# display.net
KiCad netlist of a schematic drawn in Altium Designer
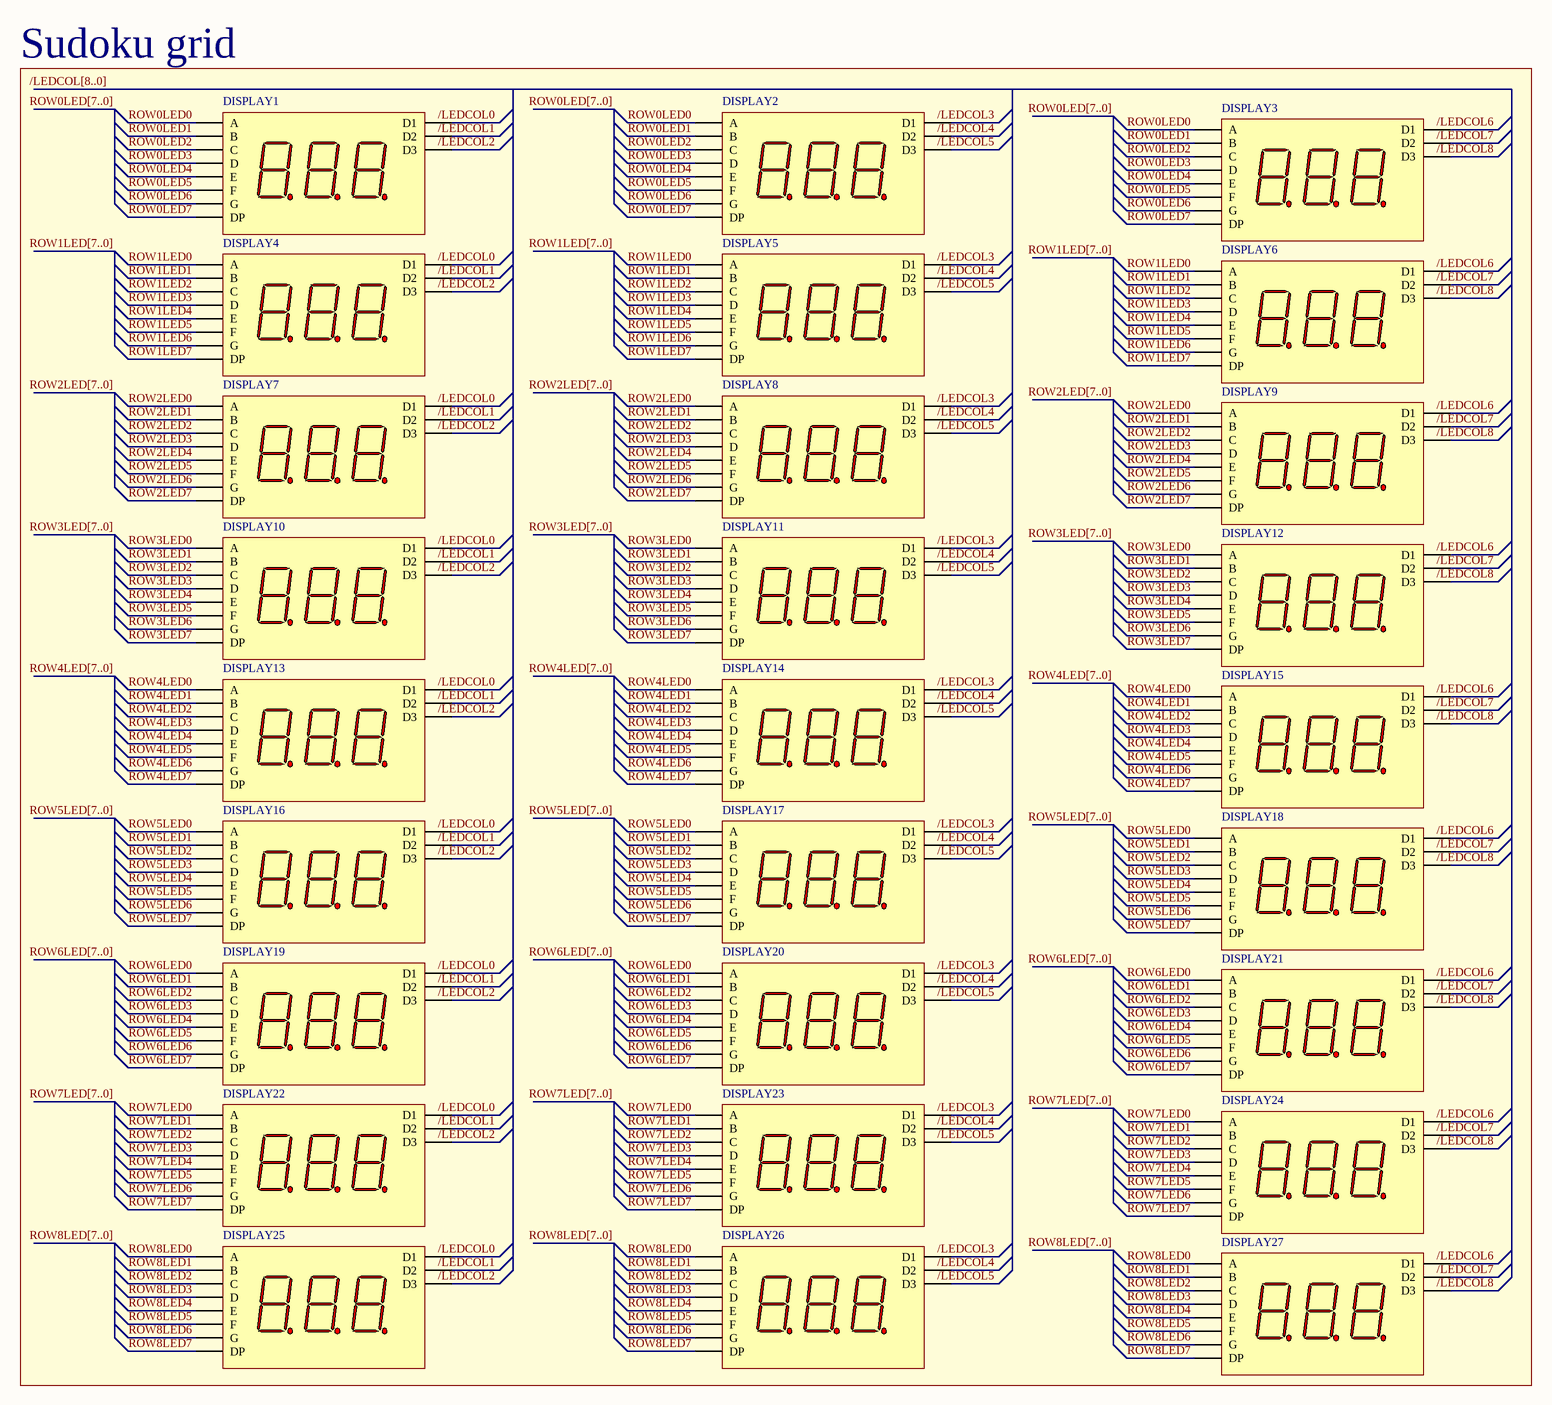
[diagram p0: display.SchDoc]

(export (version "E")
  (design (tool "Eeschema 10.0.6"))
  (components
    (comp (ref "DISPLAY1")
      (value "~")
      (footprint "3DIGITDISPLAY")
      (description "7-Segment Display")
      (fields (field (name "PUBLISHER") "Altium Limited"))
      (libsource (lib "3digit_7seg_display") (part "3DIGITREDCC"))
    )
    (comp (ref "DISPLAY2")
      (value "~")
      (footprint "3DIGITDISPLAY")
      (description "7.62 mm Black Surface HER 7-Segment Display: CC, RH DP")
      (fields (field (name "PUBLISHER") "Altium Limited"))
      (libsource (lib "3digit_7seg_display") (part "3DIGITREDCC"))
    )
    (comp (ref "DISPLAY3")
      (value "~")
      (footprint "3DIGITDISPLAY")
      (description "7.62 mm Black Surface HER 7-Segment Display: CC, RH DP")
      (fields (field (name "PUBLISHER") "Altium Limited"))
      (libsource (lib "3digit_7seg_display") (part "3DIGITREDCC"))
    )
    (comp (ref "DISPLAY4")
      (value "~")
      (footprint "3DIGITDISPLAY")
      (description "7.62 mm Black Surface HER 7-Segment Display: CC, RH DP")
      (fields (field (name "PUBLISHER") "Altium Limited"))
      (libsource (lib "3digit_7seg_display") (part "3DIGITREDCC"))
    )
    (comp (ref "DISPLAY5")
      (value "~")
      (footprint "3DIGITDISPLAY")
      (description "7.62 mm Black Surface HER 7-Segment Display: CC, RH DP")
      (fields (field (name "PUBLISHER") "Altium Limited"))
      (libsource (lib "3digit_7seg_display") (part "3DIGITREDCC"))
    )
    (comp (ref "DISPLAY6")
      (value "~")
      (footprint "3DIGITDISPLAY")
      (description "7.62 mm Black Surface HER 7-Segment Display: CC, RH DP")
      (fields (field (name "PUBLISHER") "Altium Limited"))
      (libsource (lib "3digit_7seg_display") (part "3DIGITREDCC"))
    )
    (comp (ref "DISPLAY7")
      (value "~")
      (footprint "3DIGITDISPLAY")
      (description "7.62 mm Black Surface HER 7-Segment Display: CC, RH DP")
      (fields (field (name "PUBLISHER") "Altium Limited"))
      (libsource (lib "3digit_7seg_display") (part "3DIGITREDCC"))
    )
    (comp (ref "DISPLAY8")
      (value "~")
      (footprint "3DIGITDISPLAY")
      (description "7.62 mm Black Surface HER 7-Segment Display: CC, RH DP")
      (fields (field (name "PUBLISHER") "Altium Limited"))
      (libsource (lib "3digit_7seg_display") (part "3DIGITREDCC"))
    )
    (comp (ref "DISPLAY9")
      (value "~")
      (footprint "3DIGITDISPLAY")
      (description "7.62 mm Black Surface HER 7-Segment Display: CC, RH DP")
      (fields (field (name "PUBLISHER") "Altium Limited"))
      (libsource (lib "3digit_7seg_display") (part "3DIGITREDCC"))
    )
    (comp (ref "DISPLAY10")
      (value "~")
      (footprint "3DIGITDISPLAY")
      (description "7.62 mm Black Surface HER 7-Segment Display: CC, RH DP")
      (fields (field (name "PUBLISHER") "Altium Limited"))
      (libsource (lib "3digit_7seg_display") (part "3DIGITREDCC"))
    )
    (comp (ref "DISPLAY11")
      (value "~")
      (footprint "3DIGITDISPLAY")
      (description "7.62 mm Black Surface HER 7-Segment Display: CC, RH DP")
      (fields (field (name "PUBLISHER") "Altium Limited"))
      (libsource (lib "3digit_7seg_display") (part "3DIGITREDCC"))
    )
    (comp (ref "DISPLAY12")
      (value "~")
      (footprint "3DIGITDISPLAY")
      (description "7.62 mm Black Surface HER 7-Segment Display: CC, RH DP")
      (fields (field (name "PUBLISHER") "Altium Limited"))
      (libsource (lib "3digit_7seg_display") (part "3DIGITREDCC"))
    )
    (comp (ref "DISPLAY13")
      (value "~")
      (footprint "3DIGITDISPLAY")
      (description "7.62 mm Black Surface HER 7-Segment Display: CC, RH DP")
      (fields (field (name "PUBLISHER") "Altium Limited"))
      (libsource (lib "3digit_7seg_display") (part "3DIGITREDCC"))
    )
    (comp (ref "DISPLAY14")
      (value "~")
      (footprint "3DIGITDISPLAY")
      (description "7.62 mm Black Surface HER 7-Segment Display: CC, RH DP")
      (fields (field (name "PUBLISHER") "Altium Limited"))
      (libsource (lib "3digit_7seg_display") (part "3DIGITREDCC"))
    )
    (comp (ref "DISPLAY15")
      (value "~")
      (footprint "3DIGITDISPLAY")
      (description "7.62 mm Black Surface HER 7-Segment Display: CC, RH DP")
      (fields (field (name "PUBLISHER") "Altium Limited"))
      (libsource (lib "3digit_7seg_display") (part "3DIGITREDCC"))
    )
    (comp (ref "DISPLAY16")
      (value "~")
      (footprint "3DIGITDISPLAY")
      (description "7.62 mm Black Surface HER 7-Segment Display: CC, RH DP")
      (fields (field (name "PUBLISHER") "Altium Limited"))
      (libsource (lib "3digit_7seg_display") (part "3DIGITREDCC"))
    )
    (comp (ref "DISPLAY17")
      (value "~")
      (footprint "3DIGITDISPLAY")
      (description "7.62 mm Black Surface HER 7-Segment Display: CC, RH DP")
      (fields (field (name "PUBLISHER") "Altium Limited"))
      (libsource (lib "3digit_7seg_display") (part "3DIGITREDCC"))
    )
    (comp (ref "DISPLAY18")
      (value "~")
      (footprint "3DIGITDISPLAY")
      (description "7.62 mm Black Surface HER 7-Segment Display: CC, RH DP")
      (fields (field (name "PUBLISHER") "Altium Limited"))
      (libsource (lib "3digit_7seg_display") (part "3DIGITREDCC"))
    )
    (comp (ref "DISPLAY19")
      (value "~")
      (footprint "3DIGITDISPLAY")
      (description "7.62 mm Black Surface HER 7-Segment Display: CC, RH DP")
      (fields (field (name "PUBLISHER") "Altium Limited"))
      (libsource (lib "3digit_7seg_display") (part "3DIGITREDCC"))
    )
    (comp (ref "DISPLAY20")
      (value "~")
      (footprint "3DIGITDISPLAY")
      (description "7.62 mm Black Surface HER 7-Segment Display: CC, RH DP")
      (fields (field (name "PUBLISHER") "Altium Limited"))
      (libsource (lib "3digit_7seg_display") (part "3DIGITREDCC"))
    )
    (comp (ref "DISPLAY21")
      (value "~")
      (footprint "3DIGITDISPLAY")
      (description "7.62 mm Black Surface HER 7-Segment Display: CC, RH DP")
      (fields (field (name "PUBLISHER") "Altium Limited"))
      (libsource (lib "3digit_7seg_display") (part "3DIGITREDCC"))
    )
    (comp (ref "DISPLAY22")
      (value "~")
      (footprint "3DIGITDISPLAY")
      (description "7.62 mm Black Surface HER 7-Segment Display: CC, RH DP")
      (fields (field (name "PUBLISHER") "Altium Limited"))
      (libsource (lib "3digit_7seg_display") (part "3DIGITREDCC"))
    )
    (comp (ref "DISPLAY23")
      (value "~")
      (footprint "3DIGITDISPLAY")
      (description "7.62 mm Black Surface HER 7-Segment Display: CC, RH DP")
      (fields (field (name "PUBLISHER") "Altium Limited"))
      (libsource (lib "3digit_7seg_display") (part "3DIGITREDCC"))
    )
    (comp (ref "DISPLAY24")
      (value "~")
      (footprint "3DIGITDISPLAY")
      (description "7.62 mm Black Surface HER 7-Segment Display: CC, RH DP")
      (fields (field (name "PUBLISHER") "Altium Limited"))
      (libsource (lib "3digit_7seg_display") (part "3DIGITREDCC"))
    )
    (comp (ref "DISPLAY25")
      (value "~")
      (footprint "3DIGITDISPLAY")
      (description "7.62 mm Black Surface HER 7-Segment Display: CC, RH DP")
      (fields (field (name "PUBLISHER") "Altium Limited"))
      (libsource (lib "3digit_7seg_display") (part "3DIGITREDCC"))
    )
    (comp (ref "DISPLAY26")
      (value "~")
      (footprint "3DIGITDISPLAY")
      (description "7.62 mm Black Surface HER 7-Segment Display: CC, RH DP")
      (fields (field (name "PUBLISHER") "Altium Limited"))
      (libsource (lib "3digit_7seg_display") (part "3DIGITREDCC"))
    )
    (comp (ref "DISPLAY27")
      (value "~")
      (footprint "3DIGITDISPLAY")
      (description "7.62 mm Black Surface HER 7-Segment Display: CC, RH DP")
      (fields (field (name "PUBLISHER") "Altium Limited"))
      (libsource (lib "3digit_7seg_display") (part "3DIGITREDCC"))
    )
  )
  (nets
    (net (code "10") (name "/ROW0LED0") (class "Default")
      (node (ref "DISPLAY1") (pin "11") (pinfunction "A_11") (pintype "passive"))
      (node (ref "DISPLAY2") (pin "11") (pinfunction "A_11") (pintype "passive"))
      (node (ref "DISPLAY3") (pin "11") (pinfunction "A_11") (pintype "passive"))
    )
    (net (code "11") (name "/ROW0LED1") (class "Default")
      (node (ref "DISPLAY1") (pin "7") (pinfunction "B_7") (pintype "passive"))
      (node (ref "DISPLAY2") (pin "7") (pinfunction "B_7") (pintype "passive"))
      (node (ref "DISPLAY3") (pin "7") (pinfunction "B_7") (pintype "passive"))
    )
    (net (code "12") (name "/ROW0LED2") (class "Default")
      (node (ref "DISPLAY1") (pin "4") (pinfunction "C_4") (pintype "passive"))
      (node (ref "DISPLAY2") (pin "4") (pinfunction "C_4") (pintype "passive"))
      (node (ref "DISPLAY3") (pin "4") (pinfunction "C_4") (pintype "passive"))
    )
    (net (code "13") (name "/ROW0LED3") (class "Default")
      (node (ref "DISPLAY1") (pin "2") (pinfunction "D_2") (pintype "passive"))
      (node (ref "DISPLAY2") (pin "2") (pinfunction "D_2") (pintype "passive"))
      (node (ref "DISPLAY3") (pin "2") (pinfunction "D_2") (pintype "passive"))
    )
    (net (code "14") (name "/ROW0LED4") (class "Default")
      (node (ref "DISPLAY1") (pin "1") (pinfunction "E_1") (pintype "passive"))
      (node (ref "DISPLAY2") (pin "1") (pinfunction "E_1") (pintype "passive"))
      (node (ref "DISPLAY3") (pin "1") (pinfunction "E_1") (pintype "passive"))
    )
    (net (code "15") (name "/ROW0LED5") (class "Default")
      (node (ref "DISPLAY1") (pin "10") (pinfunction "F_10") (pintype "passive"))
      (node (ref "DISPLAY2") (pin "10") (pinfunction "F_10") (pintype "passive"))
      (node (ref "DISPLAY3") (pin "10") (pinfunction "F_10") (pintype "passive"))
    )
    (net (code "16") (name "/ROW0LED6") (class "Default")
      (node (ref "DISPLAY1") (pin "5") (pinfunction "G_5") (pintype "passive"))
      (node (ref "DISPLAY2") (pin "5") (pinfunction "G_5") (pintype "passive"))
      (node (ref "DISPLAY3") (pin "5") (pinfunction "G_5") (pintype "passive"))
    )
    (net (code "17") (name "/ROW0LED7") (class "Default")
      (node (ref "DISPLAY1") (pin "3") (pinfunction "DP_3") (pintype "passive"))
      (node (ref "DISPLAY2") (pin "3") (pinfunction "DP_3") (pintype "passive"))
      (node (ref "DISPLAY3") (pin "3") (pinfunction "DP_3") (pintype "passive"))
    )
    (net (code "19") (name "/ROW1LED0") (class "Default")
      (node (ref "DISPLAY4") (pin "11") (pinfunction "A_11") (pintype "passive"))
      (node (ref "DISPLAY5") (pin "11") (pinfunction "A_11") (pintype "passive"))
      (node (ref "DISPLAY6") (pin "11") (pinfunction "A_11") (pintype "passive"))
    )
    (net (code "20") (name "/ROW1LED1") (class "Default")
      (node (ref "DISPLAY4") (pin "7") (pinfunction "B_7") (pintype "passive"))
      (node (ref "DISPLAY5") (pin "7") (pinfunction "B_7") (pintype "passive"))
      (node (ref "DISPLAY6") (pin "7") (pinfunction "B_7") (pintype "passive"))
    )
    (net (code "21") (name "/ROW1LED2") (class "Default")
      (node (ref "DISPLAY4") (pin "4") (pinfunction "C_4") (pintype "passive"))
      (node (ref "DISPLAY5") (pin "4") (pinfunction "C_4") (pintype "passive"))
      (node (ref "DISPLAY6") (pin "4") (pinfunction "C_4") (pintype "passive"))
    )
    (net (code "22") (name "/ROW1LED3") (class "Default")
      (node (ref "DISPLAY4") (pin "2") (pinfunction "D_2") (pintype "passive"))
      (node (ref "DISPLAY5") (pin "2") (pinfunction "D_2") (pintype "passive"))
      (node (ref "DISPLAY6") (pin "2") (pinfunction "D_2") (pintype "passive"))
    )
    (net (code "23") (name "/ROW1LED4") (class "Default")
      (node (ref "DISPLAY4") (pin "1") (pinfunction "E_1") (pintype "passive"))
      (node (ref "DISPLAY5") (pin "1") (pinfunction "E_1") (pintype "passive"))
      (node (ref "DISPLAY6") (pin "1") (pinfunction "E_1") (pintype "passive"))
    )
    (net (code "24") (name "/ROW1LED5") (class "Default")
      (node (ref "DISPLAY4") (pin "10") (pinfunction "F_10") (pintype "passive"))
      (node (ref "DISPLAY5") (pin "10") (pinfunction "F_10") (pintype "passive"))
      (node (ref "DISPLAY6") (pin "10") (pinfunction "F_10") (pintype "passive"))
    )
    (net (code "25") (name "/ROW1LED6") (class "Default")
      (node (ref "DISPLAY4") (pin "5") (pinfunction "G_5") (pintype "passive"))
      (node (ref "DISPLAY5") (pin "5") (pinfunction "G_5") (pintype "passive"))
      (node (ref "DISPLAY6") (pin "5") (pinfunction "G_5") (pintype "passive"))
    )
    (net (code "26") (name "/ROW1LED7") (class "Default")
      (node (ref "DISPLAY4") (pin "3") (pinfunction "DP_3") (pintype "passive"))
      (node (ref "DISPLAY5") (pin "3") (pinfunction "DP_3") (pintype "passive"))
      (node (ref "DISPLAY6") (pin "3") (pinfunction "DP_3") (pintype "passive"))
    )
    (net (code "28") (name "/ROW2LED0") (class "Default")
      (node (ref "DISPLAY7") (pin "11") (pinfunction "A_11") (pintype "passive"))
      (node (ref "DISPLAY8") (pin "11") (pinfunction "A_11") (pintype "passive"))
      (node (ref "DISPLAY9") (pin "11") (pinfunction "A_11") (pintype "passive"))
    )
    (net (code "29") (name "/ROW2LED1") (class "Default")
      (node (ref "DISPLAY7") (pin "7") (pinfunction "B_7") (pintype "passive"))
      (node (ref "DISPLAY8") (pin "7") (pinfunction "B_7") (pintype "passive"))
      (node (ref "DISPLAY9") (pin "7") (pinfunction "B_7") (pintype "passive"))
    )
    (net (code "30") (name "/ROW2LED2") (class "Default")
      (node (ref "DISPLAY7") (pin "4") (pinfunction "C_4") (pintype "passive"))
      (node (ref "DISPLAY8") (pin "4") (pinfunction "C_4") (pintype "passive"))
      (node (ref "DISPLAY9") (pin "4") (pinfunction "C_4") (pintype "passive"))
    )
    (net (code "31") (name "/ROW2LED3") (class "Default")
      (node (ref "DISPLAY7") (pin "2") (pinfunction "D_2") (pintype "passive"))
      (node (ref "DISPLAY8") (pin "2") (pinfunction "D_2") (pintype "passive"))
      (node (ref "DISPLAY9") (pin "2") (pinfunction "D_2") (pintype "passive"))
    )
    (net (code "32") (name "/ROW2LED4") (class "Default")
      (node (ref "DISPLAY7") (pin "1") (pinfunction "E_1") (pintype "passive"))
      (node (ref "DISPLAY8") (pin "1") (pinfunction "E_1") (pintype "passive"))
      (node (ref "DISPLAY9") (pin "1") (pinfunction "E_1") (pintype "passive"))
    )
    (net (code "33") (name "/ROW2LED5") (class "Default")
      (node (ref "DISPLAY7") (pin "10") (pinfunction "F_10") (pintype "passive"))
      (node (ref "DISPLAY8") (pin "10") (pinfunction "F_10") (pintype "passive"))
      (node (ref "DISPLAY9") (pin "10") (pinfunction "F_10") (pintype "passive"))
    )
    (net (code "34") (name "/ROW2LED6") (class "Default")
      (node (ref "DISPLAY7") (pin "5") (pinfunction "G_5") (pintype "passive"))
      (node (ref "DISPLAY8") (pin "5") (pinfunction "G_5") (pintype "passive"))
      (node (ref "DISPLAY9") (pin "5") (pinfunction "G_5") (pintype "passive"))
    )
    (net (code "35") (name "/ROW2LED7") (class "Default")
      (node (ref "DISPLAY7") (pin "3") (pinfunction "DP_3") (pintype "passive"))
      (node (ref "DISPLAY8") (pin "3") (pinfunction "DP_3") (pintype "passive"))
      (node (ref "DISPLAY9") (pin "3") (pinfunction "DP_3") (pintype "passive"))
    )
    (net (code "37") (name "/ROW3LED0") (class "Default")
      (node (ref "DISPLAY10") (pin "11") (pinfunction "A_11") (pintype "passive"))
      (node (ref "DISPLAY11") (pin "11") (pinfunction "A_11") (pintype "passive"))
      (node (ref "DISPLAY12") (pin "11") (pinfunction "A_11") (pintype "passive"))
    )
    (net (code "38") (name "/ROW3LED1") (class "Default")
      (node (ref "DISPLAY10") (pin "7") (pinfunction "B_7") (pintype "passive"))
      (node (ref "DISPLAY11") (pin "7") (pinfunction "B_7") (pintype "passive"))
      (node (ref "DISPLAY12") (pin "7") (pinfunction "B_7") (pintype "passive"))
    )
    (net (code "39") (name "/ROW3LED2") (class "Default")
      (node (ref "DISPLAY10") (pin "4") (pinfunction "C_4") (pintype "passive"))
      (node (ref "DISPLAY11") (pin "4") (pinfunction "C_4") (pintype "passive"))
      (node (ref "DISPLAY12") (pin "4") (pinfunction "C_4") (pintype "passive"))
    )
    (net (code "40") (name "/ROW3LED3") (class "Default")
      (node (ref "DISPLAY10") (pin "2") (pinfunction "D_2") (pintype "passive"))
      (node (ref "DISPLAY11") (pin "2") (pinfunction "D_2") (pintype "passive"))
      (node (ref "DISPLAY12") (pin "2") (pinfunction "D_2") (pintype "passive"))
    )
    (net (code "41") (name "/ROW3LED4") (class "Default")
      (node (ref "DISPLAY10") (pin "1") (pinfunction "E_1") (pintype "passive"))
      (node (ref "DISPLAY11") (pin "1") (pinfunction "E_1") (pintype "passive"))
      (node (ref "DISPLAY12") (pin "1") (pinfunction "E_1") (pintype "passive"))
    )
    (net (code "42") (name "/ROW3LED5") (class "Default")
      (node (ref "DISPLAY10") (pin "10") (pinfunction "F_10") (pintype "passive"))
      (node (ref "DISPLAY11") (pin "10") (pinfunction "F_10") (pintype "passive"))
      (node (ref "DISPLAY12") (pin "10") (pinfunction "F_10") (pintype "passive"))
    )
    (net (code "43") (name "/ROW3LED6") (class "Default")
      (node (ref "DISPLAY10") (pin "5") (pinfunction "G_5") (pintype "passive"))
      (node (ref "DISPLAY11") (pin "5") (pinfunction "G_5") (pintype "passive"))
      (node (ref "DISPLAY12") (pin "5") (pinfunction "G_5") (pintype "passive"))
    )
    (net (code "44") (name "/ROW3LED7") (class "Default")
      (node (ref "DISPLAY10") (pin "3") (pinfunction "DP_3") (pintype "passive"))
      (node (ref "DISPLAY11") (pin "3") (pinfunction "DP_3") (pintype "passive"))
      (node (ref "DISPLAY12") (pin "3") (pinfunction "DP_3") (pintype "passive"))
    )
    (net (code "46") (name "/ROW4LED0") (class "Default")
      (node (ref "DISPLAY13") (pin "11") (pinfunction "A_11") (pintype "passive"))
      (node (ref "DISPLAY14") (pin "11") (pinfunction "A_11") (pintype "passive"))
      (node (ref "DISPLAY15") (pin "11") (pinfunction "A_11") (pintype "passive"))
    )
    (net (code "47") (name "/ROW4LED1") (class "Default")
      (node (ref "DISPLAY13") (pin "7") (pinfunction "B_7") (pintype "passive"))
      (node (ref "DISPLAY14") (pin "7") (pinfunction "B_7") (pintype "passive"))
      (node (ref "DISPLAY15") (pin "7") (pinfunction "B_7") (pintype "passive"))
    )
    (net (code "48") (name "/ROW4LED2") (class "Default")
      (node (ref "DISPLAY13") (pin "4") (pinfunction "C_4") (pintype "passive"))
      (node (ref "DISPLAY14") (pin "4") (pinfunction "C_4") (pintype "passive"))
      (node (ref "DISPLAY15") (pin "4") (pinfunction "C_4") (pintype "passive"))
    )
    (net (code "49") (name "/ROW4LED3") (class "Default")
      (node (ref "DISPLAY13") (pin "2") (pinfunction "D_2") (pintype "passive"))
      (node (ref "DISPLAY14") (pin "2") (pinfunction "D_2") (pintype "passive"))
      (node (ref "DISPLAY15") (pin "2") (pinfunction "D_2") (pintype "passive"))
    )
    (net (code "50") (name "/ROW4LED4") (class "Default")
      (node (ref "DISPLAY13") (pin "1") (pinfunction "E_1") (pintype "passive"))
      (node (ref "DISPLAY14") (pin "1") (pinfunction "E_1") (pintype "passive"))
      (node (ref "DISPLAY15") (pin "1") (pinfunction "E_1") (pintype "passive"))
    )
    (net (code "51") (name "/ROW4LED5") (class "Default")
      (node (ref "DISPLAY13") (pin "10") (pinfunction "F_10") (pintype "passive"))
      (node (ref "DISPLAY14") (pin "10") (pinfunction "F_10") (pintype "passive"))
      (node (ref "DISPLAY15") (pin "10") (pinfunction "F_10") (pintype "passive"))
    )
    (net (code "52") (name "/ROW4LED6") (class "Default")
      (node (ref "DISPLAY13") (pin "5") (pinfunction "G_5") (pintype "passive"))
      (node (ref "DISPLAY14") (pin "5") (pinfunction "G_5") (pintype "passive"))
      (node (ref "DISPLAY15") (pin "5") (pinfunction "G_5") (pintype "passive"))
    )
    (net (code "53") (name "/ROW4LED7") (class "Default")
      (node (ref "DISPLAY13") (pin "3") (pinfunction "DP_3") (pintype "passive"))
      (node (ref "DISPLAY14") (pin "3") (pinfunction "DP_3") (pintype "passive"))
      (node (ref "DISPLAY15") (pin "3") (pinfunction "DP_3") (pintype "passive"))
    )
    (net (code "55") (name "/ROW5LED0") (class "Default")
      (node (ref "DISPLAY16") (pin "11") (pinfunction "A_11") (pintype "passive"))
      (node (ref "DISPLAY17") (pin "11") (pinfunction "A_11") (pintype "passive"))
      (node (ref "DISPLAY18") (pin "11") (pinfunction "A_11") (pintype "passive"))
    )
    (net (code "56") (name "/ROW5LED1") (class "Default")
      (node (ref "DISPLAY16") (pin "7") (pinfunction "B_7") (pintype "passive"))
      (node (ref "DISPLAY17") (pin "7") (pinfunction "B_7") (pintype "passive"))
      (node (ref "DISPLAY18") (pin "7") (pinfunction "B_7") (pintype "passive"))
    )
    (net (code "57") (name "/ROW5LED2") (class "Default")
      (node (ref "DISPLAY16") (pin "4") (pinfunction "C_4") (pintype "passive"))
      (node (ref "DISPLAY17") (pin "4") (pinfunction "C_4") (pintype "passive"))
      (node (ref "DISPLAY18") (pin "4") (pinfunction "C_4") (pintype "passive"))
    )
    (net (code "58") (name "/ROW5LED3") (class "Default")
      (node (ref "DISPLAY16") (pin "2") (pinfunction "D_2") (pintype "passive"))
      (node (ref "DISPLAY17") (pin "2") (pinfunction "D_2") (pintype "passive"))
      (node (ref "DISPLAY18") (pin "2") (pinfunction "D_2") (pintype "passive"))
    )
    (net (code "59") (name "/ROW5LED4") (class "Default")
      (node (ref "DISPLAY16") (pin "1") (pinfunction "E_1") (pintype "passive"))
      (node (ref "DISPLAY17") (pin "1") (pinfunction "E_1") (pintype "passive"))
      (node (ref "DISPLAY18") (pin "1") (pinfunction "E_1") (pintype "passive"))
    )
    (net (code "60") (name "/ROW5LED5") (class "Default")
      (node (ref "DISPLAY16") (pin "10") (pinfunction "F_10") (pintype "passive"))
      (node (ref "DISPLAY17") (pin "10") (pinfunction "F_10") (pintype "passive"))
      (node (ref "DISPLAY18") (pin "10") (pinfunction "F_10") (pintype "passive"))
    )
    (net (code "61") (name "/ROW5LED6") (class "Default")
      (node (ref "DISPLAY16") (pin "5") (pinfunction "G_5") (pintype "passive"))
      (node (ref "DISPLAY17") (pin "5") (pinfunction "G_5") (pintype "passive"))
      (node (ref "DISPLAY18") (pin "5") (pinfunction "G_5") (pintype "passive"))
    )
    (net (code "62") (name "/ROW5LED7") (class "Default")
      (node (ref "DISPLAY16") (pin "3") (pinfunction "DP_3") (pintype "passive"))
      (node (ref "DISPLAY17") (pin "3") (pinfunction "DP_3") (pintype "passive"))
      (node (ref "DISPLAY18") (pin "3") (pinfunction "DP_3") (pintype "passive"))
    )
    (net (code "64") (name "/ROW6LED0") (class "Default")
      (node (ref "DISPLAY19") (pin "11") (pinfunction "A_11") (pintype "passive"))
      (node (ref "DISPLAY20") (pin "11") (pinfunction "A_11") (pintype "passive"))
      (node (ref "DISPLAY21") (pin "11") (pinfunction "A_11") (pintype "passive"))
    )
    (net (code "65") (name "/ROW6LED1") (class "Default")
      (node (ref "DISPLAY19") (pin "7") (pinfunction "B_7") (pintype "passive"))
      (node (ref "DISPLAY20") (pin "7") (pinfunction "B_7") (pintype "passive"))
      (node (ref "DISPLAY21") (pin "7") (pinfunction "B_7") (pintype "passive"))
    )
    (net (code "66") (name "/ROW6LED2") (class "Default")
      (node (ref "DISPLAY19") (pin "4") (pinfunction "C_4") (pintype "passive"))
      (node (ref "DISPLAY20") (pin "4") (pinfunction "C_4") (pintype "passive"))
      (node (ref "DISPLAY21") (pin "4") (pinfunction "C_4") (pintype "passive"))
    )
    (net (code "67") (name "/ROW6LED3") (class "Default")
      (node (ref "DISPLAY19") (pin "2") (pinfunction "D_2") (pintype "passive"))
      (node (ref "DISPLAY20") (pin "2") (pinfunction "D_2") (pintype "passive"))
      (node (ref "DISPLAY21") (pin "2") (pinfunction "D_2") (pintype "passive"))
    )
    (net (code "68") (name "/ROW6LED4") (class "Default")
      (node (ref "DISPLAY19") (pin "1") (pinfunction "E_1") (pintype "passive"))
      (node (ref "DISPLAY20") (pin "1") (pinfunction "E_1") (pintype "passive"))
      (node (ref "DISPLAY21") (pin "1") (pinfunction "E_1") (pintype "passive"))
    )
    (net (code "69") (name "/ROW6LED5") (class "Default")
      (node (ref "DISPLAY19") (pin "10") (pinfunction "F_10") (pintype "passive"))
      (node (ref "DISPLAY20") (pin "10") (pinfunction "F_10") (pintype "passive"))
      (node (ref "DISPLAY21") (pin "10") (pinfunction "F_10") (pintype "passive"))
    )
    (net (code "70") (name "/ROW6LED6") (class "Default")
      (node (ref "DISPLAY19") (pin "5") (pinfunction "G_5") (pintype "passive"))
      (node (ref "DISPLAY20") (pin "5") (pinfunction "G_5") (pintype "passive"))
      (node (ref "DISPLAY21") (pin "5") (pinfunction "G_5") (pintype "passive"))
    )
    (net (code "71") (name "/ROW6LED7") (class "Default")
      (node (ref "DISPLAY19") (pin "3") (pinfunction "DP_3") (pintype "passive"))
      (node (ref "DISPLAY20") (pin "3") (pinfunction "DP_3") (pintype "passive"))
      (node (ref "DISPLAY21") (pin "3") (pinfunction "DP_3") (pintype "passive"))
    )
    (net (code "73") (name "/ROW7LED0") (class "Default")
      (node (ref "DISPLAY22") (pin "11") (pinfunction "A_11") (pintype "passive"))
      (node (ref "DISPLAY23") (pin "11") (pinfunction "A_11") (pintype "passive"))
      (node (ref "DISPLAY24") (pin "11") (pinfunction "A_11") (pintype "passive"))
    )
    (net (code "74") (name "/ROW7LED1") (class "Default")
      (node (ref "DISPLAY22") (pin "7") (pinfunction "B_7") (pintype "passive"))
      (node (ref "DISPLAY23") (pin "7") (pinfunction "B_7") (pintype "passive"))
      (node (ref "DISPLAY24") (pin "7") (pinfunction "B_7") (pintype "passive"))
    )
    (net (code "75") (name "/ROW7LED2") (class "Default")
      (node (ref "DISPLAY22") (pin "4") (pinfunction "C_4") (pintype "passive"))
      (node (ref "DISPLAY23") (pin "4") (pinfunction "C_4") (pintype "passive"))
      (node (ref "DISPLAY24") (pin "4") (pinfunction "C_4") (pintype "passive"))
    )
    (net (code "76") (name "/ROW7LED3") (class "Default")
      (node (ref "DISPLAY22") (pin "2") (pinfunction "D_2") (pintype "passive"))
      (node (ref "DISPLAY23") (pin "2") (pinfunction "D_2") (pintype "passive"))
      (node (ref "DISPLAY24") (pin "2") (pinfunction "D_2") (pintype "passive"))
    )
    (net (code "77") (name "/ROW7LED4") (class "Default")
      (node (ref "DISPLAY22") (pin "1") (pinfunction "E_1") (pintype "passive"))
      (node (ref "DISPLAY23") (pin "1") (pinfunction "E_1") (pintype "passive"))
      (node (ref "DISPLAY24") (pin "1") (pinfunction "E_1") (pintype "passive"))
    )
    (net (code "78") (name "/ROW7LED5") (class "Default")
      (node (ref "DISPLAY22") (pin "10") (pinfunction "F_10") (pintype "passive"))
      (node (ref "DISPLAY23") (pin "10") (pinfunction "F_10") (pintype "passive"))
      (node (ref "DISPLAY24") (pin "10") (pinfunction "F_10") (pintype "passive"))
    )
    (net (code "79") (name "/ROW7LED6") (class "Default")
      (node (ref "DISPLAY22") (pin "5") (pinfunction "G_5") (pintype "passive"))
      (node (ref "DISPLAY23") (pin "5") (pinfunction "G_5") (pintype "passive"))
      (node (ref "DISPLAY24") (pin "5") (pinfunction "G_5") (pintype "passive"))
    )
    (net (code "80") (name "/ROW7LED7") (class "Default")
      (node (ref "DISPLAY22") (pin "3") (pinfunction "DP_3") (pintype "passive"))
      (node (ref "DISPLAY23") (pin "3") (pinfunction "DP_3") (pintype "passive"))
      (node (ref "DISPLAY24") (pin "3") (pinfunction "DP_3") (pintype "passive"))
    )
    (net (code "82") (name "/ROW8LED0") (class "Default")
      (node (ref "DISPLAY25") (pin "11") (pinfunction "A_11") (pintype "passive"))
      (node (ref "DISPLAY26") (pin "11") (pinfunction "A_11") (pintype "passive"))
      (node (ref "DISPLAY27") (pin "11") (pinfunction "A_11") (pintype "passive"))
    )
    (net (code "83") (name "/ROW8LED1") (class "Default")
      (node (ref "DISPLAY25") (pin "7") (pinfunction "B_7") (pintype "passive"))
      (node (ref "DISPLAY26") (pin "7") (pinfunction "B_7") (pintype "passive"))
      (node (ref "DISPLAY27") (pin "7") (pinfunction "B_7") (pintype "passive"))
    )
    (net (code "84") (name "/ROW8LED2") (class "Default")
      (node (ref "DISPLAY25") (pin "4") (pinfunction "C_4") (pintype "passive"))
      (node (ref "DISPLAY26") (pin "4") (pinfunction "C_4") (pintype "passive"))
      (node (ref "DISPLAY27") (pin "4") (pinfunction "C_4") (pintype "passive"))
    )
    (net (code "85") (name "/ROW8LED3") (class "Default")
      (node (ref "DISPLAY25") (pin "2") (pinfunction "D_2") (pintype "passive"))
      (node (ref "DISPLAY26") (pin "2") (pinfunction "D_2") (pintype "passive"))
      (node (ref "DISPLAY27") (pin "2") (pinfunction "D_2") (pintype "passive"))
    )
    (net (code "86") (name "/ROW8LED4") (class "Default")
      (node (ref "DISPLAY25") (pin "1") (pinfunction "E_1") (pintype "passive"))
      (node (ref "DISPLAY26") (pin "1") (pinfunction "E_1") (pintype "passive"))
      (node (ref "DISPLAY27") (pin "1") (pinfunction "E_1") (pintype "passive"))
    )
    (net (code "87") (name "/ROW8LED5") (class "Default")
      (node (ref "DISPLAY25") (pin "10") (pinfunction "F_10") (pintype "passive"))
      (node (ref "DISPLAY26") (pin "10") (pinfunction "F_10") (pintype "passive"))
      (node (ref "DISPLAY27") (pin "10") (pinfunction "F_10") (pintype "passive"))
    )
    (net (code "88") (name "/ROW8LED6") (class "Default")
      (node (ref "DISPLAY25") (pin "5") (pinfunction "G_5") (pintype "passive"))
      (node (ref "DISPLAY26") (pin "5") (pinfunction "G_5") (pintype "passive"))
      (node (ref "DISPLAY27") (pin "5") (pinfunction "G_5") (pintype "passive"))
    )
    (net (code "89") (name "/ROW8LED7") (class "Default")
      (node (ref "DISPLAY25") (pin "3") (pinfunction "DP_3") (pintype "passive"))
      (node (ref "DISPLAY26") (pin "3") (pinfunction "DP_3") (pintype "passive"))
      (node (ref "DISPLAY27") (pin "3") (pinfunction "DP_3") (pintype "passive"))
    )
    (net (code "91") (name "/{slash}LEDCOL0") (class "Default")
      (node (ref "DISPLAY1") (pin "12") (pinfunction "D1_12") (pintype "passive"))
      (node (ref "DISPLAY10") (pin "12") (pinfunction "D1_12") (pintype "passive"))
      (node (ref "DISPLAY13") (pin "12") (pinfunction "D1_12") (pintype "passive"))
      (node (ref "DISPLAY16") (pin "12") (pinfunction "D1_12") (pintype "passive"))
      (node (ref "DISPLAY19") (pin "12") (pinfunction "D1_12") (pintype "passive"))
      (node (ref "DISPLAY22") (pin "12") (pinfunction "D1_12") (pintype "passive"))
      (node (ref "DISPLAY25") (pin "12") (pinfunction "D1_12") (pintype "passive"))
      (node (ref "DISPLAY4") (pin "12") (pinfunction "D1_12") (pintype "passive"))
      (node (ref "DISPLAY7") (pin "12") (pinfunction "D1_12") (pintype "passive"))
    )
    (net (code "92") (name "/{slash}LEDCOL1") (class "Default")
      (node (ref "DISPLAY1") (pin "9") (pinfunction "D2_9") (pintype "passive"))
      (node (ref "DISPLAY10") (pin "9") (pinfunction "D2_9") (pintype "passive"))
      (node (ref "DISPLAY13") (pin "9") (pinfunction "D2_9") (pintype "passive"))
      (node (ref "DISPLAY16") (pin "9") (pinfunction "D2_9") (pintype "passive"))
      (node (ref "DISPLAY19") (pin "9") (pinfunction "D2_9") (pintype "passive"))
      (node (ref "DISPLAY22") (pin "9") (pinfunction "D2_9") (pintype "passive"))
      (node (ref "DISPLAY25") (pin "9") (pinfunction "D2_9") (pintype "passive"))
      (node (ref "DISPLAY4") (pin "9") (pinfunction "D2_9") (pintype "passive"))
      (node (ref "DISPLAY7") (pin "9") (pinfunction "D2_9") (pintype "passive"))
    )
    (net (code "93") (name "/{slash}LEDCOL2") (class "Default")
      (node (ref "DISPLAY1") (pin "8") (pinfunction "D3_8") (pintype "passive"))
      (node (ref "DISPLAY10") (pin "8") (pinfunction "D3_8") (pintype "passive"))
      (node (ref "DISPLAY13") (pin "8") (pinfunction "D3_8") (pintype "passive"))
      (node (ref "DISPLAY16") (pin "8") (pinfunction "D3_8") (pintype "passive"))
      (node (ref "DISPLAY19") (pin "8") (pinfunction "D3_8") (pintype "passive"))
      (node (ref "DISPLAY22") (pin "8") (pinfunction "D3_8") (pintype "passive"))
      (node (ref "DISPLAY25") (pin "8") (pinfunction "D3_8") (pintype "passive"))
      (node (ref "DISPLAY4") (pin "8") (pinfunction "D3_8") (pintype "passive"))
      (node (ref "DISPLAY7") (pin "8") (pinfunction "D3_8") (pintype "passive"))
    )
    (net (code "94") (name "/{slash}LEDCOL3") (class "Default")
      (node (ref "DISPLAY11") (pin "12") (pinfunction "D1_12") (pintype "passive"))
      (node (ref "DISPLAY14") (pin "12") (pinfunction "D1_12") (pintype "passive"))
      (node (ref "DISPLAY17") (pin "12") (pinfunction "D1_12") (pintype "passive"))
      (node (ref "DISPLAY2") (pin "12") (pinfunction "D1_12") (pintype "passive"))
      (node (ref "DISPLAY20") (pin "12") (pinfunction "D1_12") (pintype "passive"))
      (node (ref "DISPLAY23") (pin "12") (pinfunction "D1_12") (pintype "passive"))
      (node (ref "DISPLAY26") (pin "12") (pinfunction "D1_12") (pintype "passive"))
      (node (ref "DISPLAY5") (pin "12") (pinfunction "D1_12") (pintype "passive"))
      (node (ref "DISPLAY8") (pin "12") (pinfunction "D1_12") (pintype "passive"))
    )
    (net (code "95") (name "/{slash}LEDCOL4") (class "Default")
      (node (ref "DISPLAY11") (pin "9") (pinfunction "D2_9") (pintype "passive"))
      (node (ref "DISPLAY14") (pin "9") (pinfunction "D2_9") (pintype "passive"))
      (node (ref "DISPLAY17") (pin "9") (pinfunction "D2_9") (pintype "passive"))
      (node (ref "DISPLAY2") (pin "9") (pinfunction "D2_9") (pintype "passive"))
      (node (ref "DISPLAY20") (pin "9") (pinfunction "D2_9") (pintype "passive"))
      (node (ref "DISPLAY23") (pin "9") (pinfunction "D2_9") (pintype "passive"))
      (node (ref "DISPLAY26") (pin "9") (pinfunction "D2_9") (pintype "passive"))
      (node (ref "DISPLAY5") (pin "9") (pinfunction "D2_9") (pintype "passive"))
      (node (ref "DISPLAY8") (pin "9") (pinfunction "D2_9") (pintype "passive"))
    )
    (net (code "96") (name "/{slash}LEDCOL5") (class "Default")
      (node (ref "DISPLAY11") (pin "8") (pinfunction "D3_8") (pintype "passive"))
      (node (ref "DISPLAY14") (pin "8") (pinfunction "D3_8") (pintype "passive"))
      (node (ref "DISPLAY17") (pin "8") (pinfunction "D3_8") (pintype "passive"))
      (node (ref "DISPLAY2") (pin "8") (pinfunction "D3_8") (pintype "passive"))
      (node (ref "DISPLAY20") (pin "8") (pinfunction "D3_8") (pintype "passive"))
      (node (ref "DISPLAY23") (pin "8") (pinfunction "D3_8") (pintype "passive"))
      (node (ref "DISPLAY26") (pin "8") (pinfunction "D3_8") (pintype "passive"))
      (node (ref "DISPLAY5") (pin "8") (pinfunction "D3_8") (pintype "passive"))
      (node (ref "DISPLAY8") (pin "8") (pinfunction "D3_8") (pintype "passive"))
    )
    (net (code "97") (name "/{slash}LEDCOL6") (class "Default")
      (node (ref "DISPLAY12") (pin "12") (pinfunction "D1_12") (pintype "passive"))
      (node (ref "DISPLAY15") (pin "12") (pinfunction "D1_12") (pintype "passive"))
      (node (ref "DISPLAY18") (pin "12") (pinfunction "D1_12") (pintype "passive"))
      (node (ref "DISPLAY21") (pin "12") (pinfunction "D1_12") (pintype "passive"))
      (node (ref "DISPLAY24") (pin "12") (pinfunction "D1_12") (pintype "passive"))
      (node (ref "DISPLAY27") (pin "12") (pinfunction "D1_12") (pintype "passive"))
      (node (ref "DISPLAY3") (pin "12") (pinfunction "D1_12") (pintype "passive"))
      (node (ref "DISPLAY6") (pin "12") (pinfunction "D1_12") (pintype "passive"))
      (node (ref "DISPLAY9") (pin "12") (pinfunction "D1_12") (pintype "passive"))
    )
    (net (code "98") (name "/{slash}LEDCOL7") (class "Default")
      (node (ref "DISPLAY12") (pin "9") (pinfunction "D2_9") (pintype "passive"))
      (node (ref "DISPLAY15") (pin "9") (pinfunction "D2_9") (pintype "passive"))
      (node (ref "DISPLAY18") (pin "9") (pinfunction "D2_9") (pintype "passive"))
      (node (ref "DISPLAY21") (pin "9") (pinfunction "D2_9") (pintype "passive"))
      (node (ref "DISPLAY24") (pin "9") (pinfunction "D2_9") (pintype "passive"))
      (node (ref "DISPLAY27") (pin "9") (pinfunction "D2_9") (pintype "passive"))
      (node (ref "DISPLAY3") (pin "9") (pinfunction "D2_9") (pintype "passive"))
      (node (ref "DISPLAY6") (pin "9") (pinfunction "D2_9") (pintype "passive"))
      (node (ref "DISPLAY9") (pin "9") (pinfunction "D2_9") (pintype "passive"))
    )
    (net (code "99") (name "/{slash}LEDCOL8") (class "Default")
      (node (ref "DISPLAY12") (pin "8") (pinfunction "D3_8") (pintype "passive"))
      (node (ref "DISPLAY15") (pin "8") (pinfunction "D3_8") (pintype "passive"))
      (node (ref "DISPLAY18") (pin "8") (pinfunction "D3_8") (pintype "passive"))
      (node (ref "DISPLAY21") (pin "8") (pinfunction "D3_8") (pintype "passive"))
      (node (ref "DISPLAY24") (pin "8") (pinfunction "D3_8") (pintype "passive"))
      (node (ref "DISPLAY27") (pin "8") (pinfunction "D3_8") (pintype "passive"))
      (node (ref "DISPLAY3") (pin "8") (pinfunction "D3_8") (pintype "passive"))
      (node (ref "DISPLAY6") (pin "8") (pinfunction "D3_8") (pintype "passive"))
      (node (ref "DISPLAY9") (pin "8") (pinfunction "D3_8") (pintype "passive"))
    )
  )
)
